# OSO-SCAP-B1-01_Minimalist_SAMD11_Sensor_.net
KiCad netlist of a schematic drawn in EAGLE
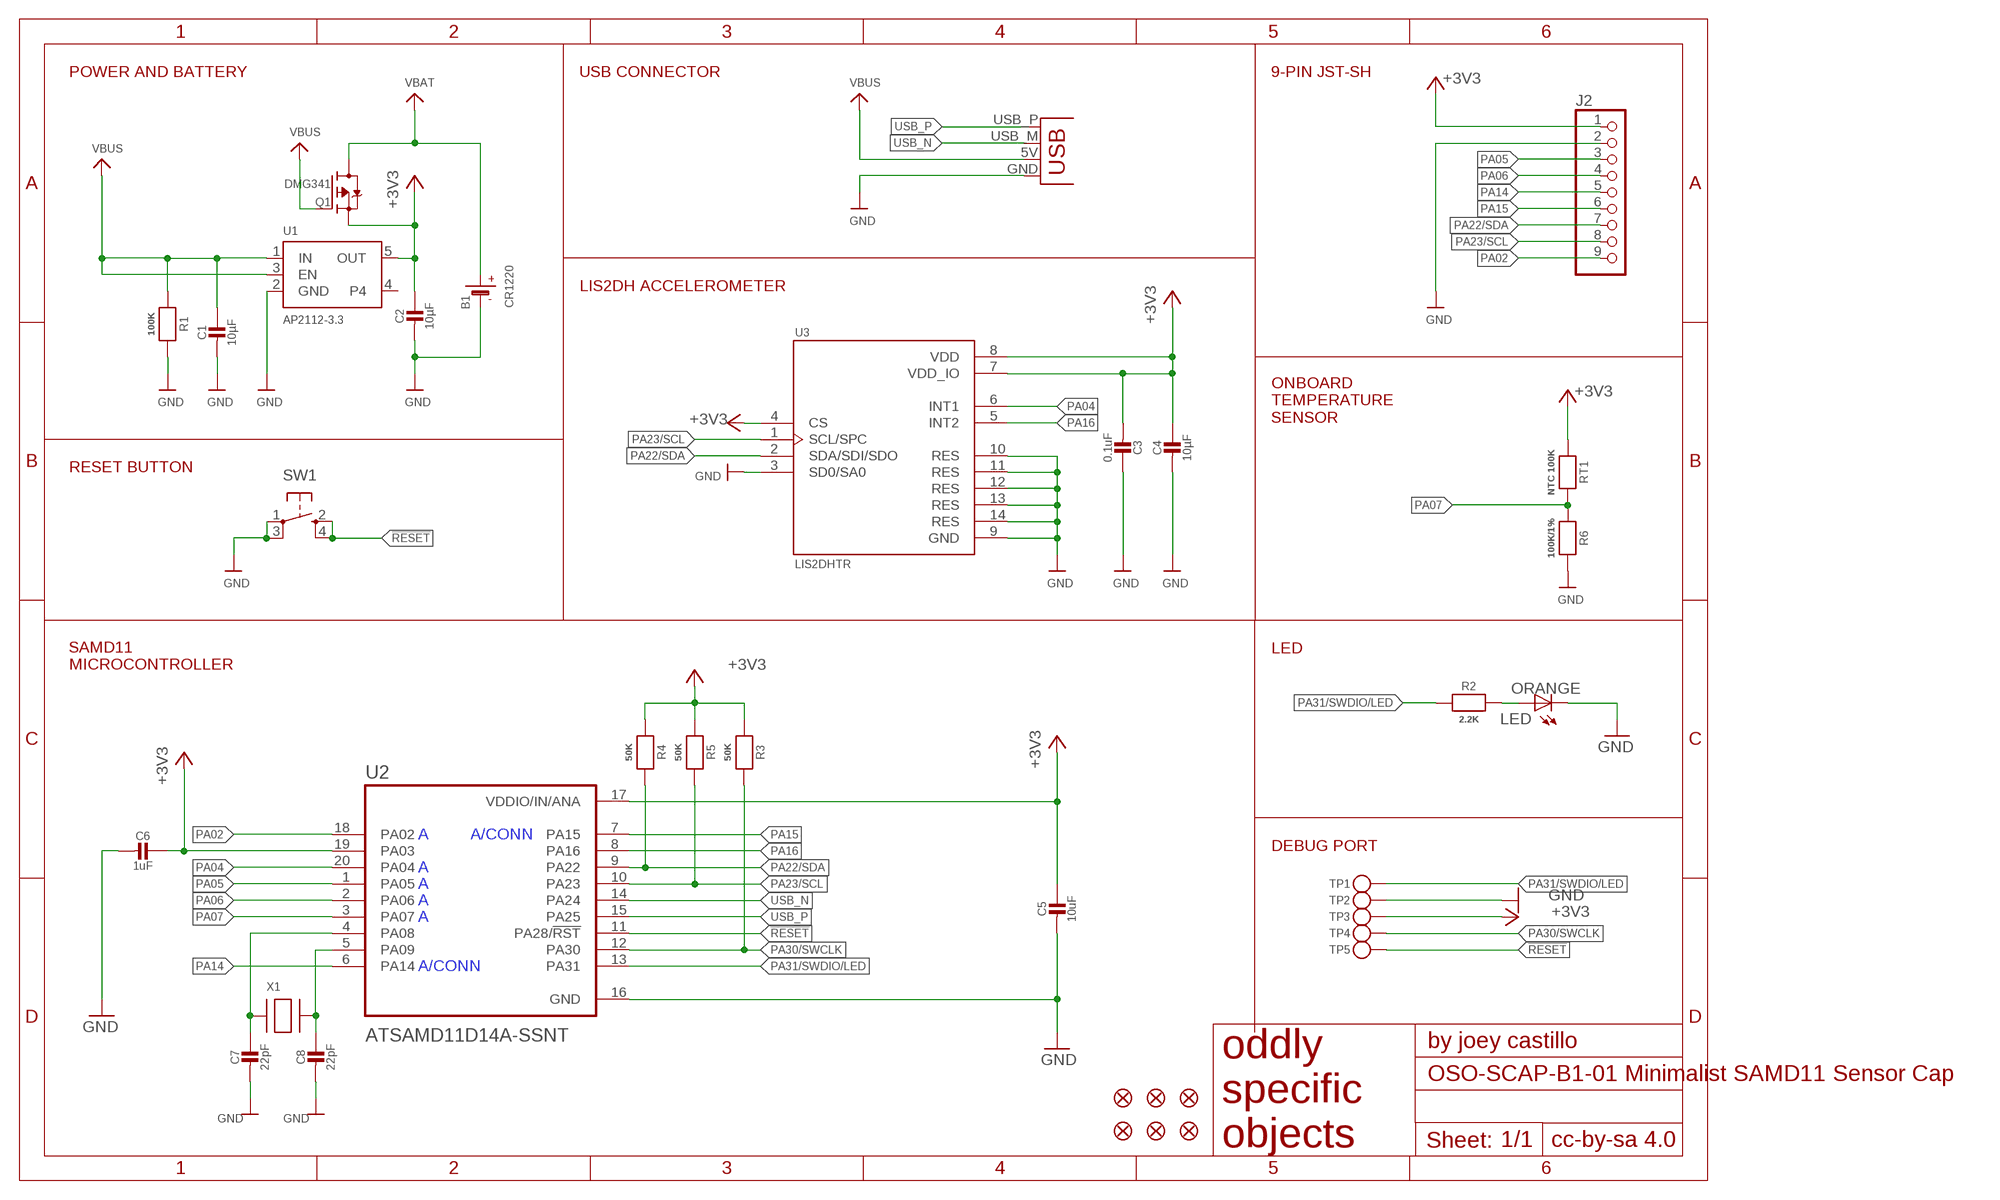
[diagram p0: schematic, sheet 1]

(export (version "E")
  (design (tool "Eeschema 10.0.6"))
  (components
    (comp (ref "B1")
      (value "CR1220")
      (footprint "eagle-import:CR1220")
      (libsource (lib "eagle-import") (part "BATTERYCR1220_SMT"))
    )
    (comp (ref "C1")
      (value "10µF")
      (footprint "eagle-import:0805-NO")
      (libsource (lib "eagle-import") (part "CAP_CERAMIC0805-NOOUTLINE"))
    )
    (comp (ref "C2")
      (value "10µF")
      (footprint "eagle-import:0805-NO")
      (libsource (lib "eagle-import") (part "CAP_CERAMIC0805-NOOUTLINE"))
    )
    (comp (ref "C3")
      (value "0.1uF")
      (footprint "eagle-import:0805-NO")
      (libsource (lib "eagle-import") (part "CAP_CERAMIC0805-NOOUTLINE"))
    )
    (comp (ref "C4")
      (value "10µF")
      (footprint "eagle-import:0805-NO")
      (libsource (lib "eagle-import") (part "CAP_CERAMIC0805-NOOUTLINE"))
    )
    (comp (ref "C5")
      (value "10uF")
      (footprint "eagle-import:0805-NO")
      (libsource (lib "eagle-import") (part "CAP_CERAMIC0805-NOOUTLINE"))
    )
    (comp (ref "C6")
      (value "1uF")
      (footprint "eagle-import:0805-NO")
      (libsource (lib "eagle-import") (part "CAP_CERAMIC0805-NOOUTLINE"))
    )
    (comp (ref "C7")
      (value "22pF")
      (footprint "eagle-import:0805-NO")
      (libsource (lib "eagle-import") (part "CAP_CERAMIC0805-NOOUTLINE"))
    )
    (comp (ref "C8")
      (value "22pF")
      (footprint "eagle-import:0805-NO")
      (libsource (lib "eagle-import") (part "CAP_CERAMIC0805-NOOUTLINE"))
    )
    (comp (ref "FID1")
      (value "FIDUCIAL_1MM")
      (footprint "eagle-import:FIDUCIAL_1MM")
      (libsource (lib "eagle-import") (part "FIDUCIAL_1MM"))
    )
    (comp (ref "FID2")
      (value "FIDUCIAL_1MM")
      (footprint "eagle-import:FIDUCIAL_1MM")
      (libsource (lib "eagle-import") (part "FIDUCIAL_1MM"))
    )
    (comp (ref "FID3")
      (value "FIDUCIAL_1MM")
      (footprint "eagle-import:FIDUCIAL_1MM")
      (libsource (lib "eagle-import") (part "FIDUCIAL_1MM"))
    )
    (comp (ref "FID4")
      (value "FIDUCIAL_1MM")
      (footprint "eagle-import:FIDUCIAL_1MM")
      (libsource (lib "eagle-import") (part "FIDUCIAL_1MM"))
    )
    (comp (ref "FID5")
      (value "FIDUCIAL_1MM")
      (footprint "eagle-import:FIDUCIAL_1MM")
      (libsource (lib "eagle-import") (part "FIDUCIAL_1MM"))
    )
    (comp (ref "FID6")
      (value "FIDUCIAL_1MM")
      (footprint "eagle-import:FIDUCIAL_1MM")
      (libsource (lib "eagle-import") (part "FIDUCIAL_1MM"))
    )
    (comp (ref "J1")
      (value "USBPCB")
      (footprint "eagle-import:USB-A-PCB")
      (libsource (lib "eagle-import") (part "USBPCB"))
    )
    (comp (ref "J2")
      (value "HEADER-1X9_JSTSH")
      (footprint "eagle-import:JST_SH9")
      (libsource (lib "eagle-import") (part "HEADER-1X9_JSTSH"))
    )
    (comp (ref "LED")
      (value "ORANGE")
      (footprint "eagle-import:CHIP-LED0805")
      (libsource (lib "eagle-import") (part "LEDCHIP-LED0805"))
    )
    (comp (ref "Q1")
      (value "DMG341")
      (footprint "eagle-import:SOT23-R")
      (libsource (lib "eagle-import") (part "MOSFET-P"))
    )
    (comp (ref "R1")
      (value "100K")
      (footprint "eagle-import:0805-NO")
      (libsource (lib "eagle-import") (part "RESISTOR0805_NOOUTLINE"))
    )
    (comp (ref "R2")
      (value "2.2K")
      (footprint "eagle-import:0805-NO")
      (libsource (lib "eagle-import") (part "RESISTOR0805_NOOUTLINE"))
    )
    (comp (ref "R3")
      (value "50K")
      (footprint "eagle-import:0805-NO")
      (libsource (lib "eagle-import") (part "RESISTOR0805_NOOUTLINE"))
    )
    (comp (ref "R4")
      (value "50K")
      (footprint "eagle-import:0805-NO")
      (libsource (lib "eagle-import") (part "RESISTOR0805_NOOUTLINE"))
    )
    (comp (ref "R5")
      (value "50K")
      (footprint "eagle-import:0805-NO")
      (libsource (lib "eagle-import") (part "RESISTOR0805_NOOUTLINE"))
    )
    (comp (ref "R6")
      (value "100K/1%")
      (footprint "eagle-import:0805-NO")
      (libsource (lib "eagle-import") (part "RESISTOR0805_NOOUTLINE"))
    )
    (comp (ref "RT1")
      (value "NTC 100K")
      (footprint "eagle-import:0805-NO")
      (libsource (lib "eagle-import") (part "RESISTOR0805_NOOUTLINE"))
    )
    (comp (ref "SW1")
      (value "SPST_TACT-KMR2")
      (footprint "eagle-import:KMR2")
      (libsource (lib "eagle-import") (part "SPST_TACT-KMR2"))
    )
    (comp (ref "TP1")
      (value "TESTPOINTROUND2MMNO")
      (footprint "eagle-import:TESTPOINT_ROUND_2MM_NO")
      (libsource (lib "eagle-import") (part "TESTPOINTROUND2MMNO"))
    )
    (comp (ref "TP2")
      (value "TESTPOINTROUND2MMNO")
      (footprint "eagle-import:TESTPOINT_ROUND_2MM_NO")
      (libsource (lib "eagle-import") (part "TESTPOINTROUND2MMNO"))
    )
    (comp (ref "TP3")
      (value "TESTPOINTROUND2MMNO")
      (footprint "eagle-import:TESTPOINT_ROUND_2MM_NO")
      (libsource (lib "eagle-import") (part "TESTPOINTROUND2MMNO"))
    )
    (comp (ref "TP4")
      (value "TESTPOINTROUND2MMNO")
      (footprint "eagle-import:TESTPOINT_ROUND_2MM_NO")
      (libsource (lib "eagle-import") (part "TESTPOINTROUND2MMNO"))
    )
    (comp (ref "TP5")
      (value "TESTPOINTROUND2MMNO")
      (footprint "eagle-import:TESTPOINT_ROUND_2MM_NO")
      (libsource (lib "eagle-import") (part "TESTPOINTROUND2MMNO"))
    )
    (comp (ref "U1")
      (value "AP2112-3.3")
      (footprint "eagle-import:SOT23-5")
      (libsource (lib "eagle-import") (part "VREG_SOT23-5"))
    )
    (comp (ref "U2")
      (value "ATSAMD11D14A-SSNT")
      (footprint "eagle-import:SOIC127P1030X265-20N")
      (fields (field (name "MF") "Microchip"))
      (libsource (lib "eagle-import") (part "ATSAMD11D14A-SSNT"))
    )
    (comp (ref "U3")
      (value "LIS2DHTR")
      (footprint "eagle-import:PQFN35P200X200X100-14N")
      (fields (field (name "DIGI-KEY_PART_NUMBER") "497-13795-1-ND") (field (name "MF") "STMicroelectronics"))
      (libsource (lib "eagle-import") (part "LIS2DHTR"))
    )
    (comp (ref "X1")
      (value "XTAL-3.2X1.5")
      (footprint "eagle-import:XTAL3215")
      (libsource (lib "eagle-import") (part "XTAL-3.2X1.5"))
    )
  )
  (nets
    (net (code "1") (name "+3V3") (class "Default")
      (node (ref "C2") (pin "1") (pinfunction "1_1") (pintype "passive"))
      (node (ref "C3") (pin "2") (pinfunction "2_2") (pintype "passive"))
      (node (ref "C4") (pin "1") (pinfunction "1_1") (pintype "passive"))
      (node (ref "C5") (pin "1") (pinfunction "1_1") (pintype "passive"))
      (node (ref "C6") (pin "1") (pinfunction "1_1") (pintype "passive"))
      (node (ref "J2") (pin "1") (pinfunction "1_1") (pintype "passive"))
      (node (ref "Q1") (pin "2") (pinfunction "S_2") (pintype "passive"))
      (node (ref "R3") (pin "1") (pinfunction "1_1") (pintype "passive"))
      (node (ref "R4") (pin "1") (pinfunction "1_1") (pintype "passive"))
      (node (ref "R5") (pin "1") (pinfunction "1_1") (pintype "passive"))
      (node (ref "RT1") (pin "1") (pinfunction "1_1") (pintype "passive"))
      (node (ref "TP3") (pin "P$1") (pinfunction "P$1_P$1") (pintype "bidirectional"))
      (node (ref "U1") (pin "5") (pinfunction "OUT_5") (pintype "power_in"))
      (node (ref "U2") (pin "17") (pinfunction "VDDIO/IN/ANA_17") (pintype "power_in"))
      (node (ref "U2") (pin "19") (pinfunction "PA03_19") (pintype "bidirectional"))
      (node (ref "U3") (pin "4") (pinfunction "CS_4") (pintype "input"))
      (node (ref "U3") (pin "7") (pinfunction "VDD_IO_7") (pintype "power_in"))
      (node (ref "U3") (pin "8") (pinfunction "VDD_8") (pintype "power_in"))
    )
    (net (code "2") (name "/~{RESET}") (class "Default")
      (node (ref "SW1") (pin "2") (pinfunction "S_2") (pintype "passive"))
      (node (ref "SW1") (pin "4") (pinfunction "S1_4") (pintype "passive"))
      (node (ref "TP5") (pin "P$1") (pinfunction "P$1_P$1") (pintype "bidirectional"))
      (node (ref "U2") (pin "11") (pinfunction "PA28/~{RST}_11") (pintype "bidirectional"))
    )
    (net (code "3") (name "GND") (class "Default")
      (node (ref "B1") (pin "-") (pinfunction "-_-") (pintype "passive"))
      (node (ref "C1") (pin "2") (pinfunction "2_2") (pintype "passive"))
      (node (ref "C2") (pin "2") (pinfunction "2_2") (pintype "passive"))
      (node (ref "C3") (pin "1") (pinfunction "1_1") (pintype "passive"))
      (node (ref "C4") (pin "2") (pinfunction "2_2") (pintype "passive"))
      (node (ref "C5") (pin "2") (pinfunction "2_2") (pintype "passive"))
      (node (ref "C6") (pin "2") (pinfunction "2_2") (pintype "passive"))
      (node (ref "C7") (pin "2") (pinfunction "2_2") (pintype "passive"))
      (node (ref "C8") (pin "2") (pinfunction "2_2") (pintype "passive"))
      (node (ref "J1") (pin "GND") (pinfunction "GND_GND") (pintype "bidirectional"))
      (node (ref "J2") (pin "2") (pinfunction "2_2") (pintype "passive"))
      (node (ref "LED") (pin "C") (pinfunction "C_C") (pintype "passive"))
      (node (ref "R1") (pin "2") (pinfunction "2_2") (pintype "passive"))
      (node (ref "R6") (pin "2") (pinfunction "2_2") (pintype "passive"))
      (node (ref "SW1") (pin "1") (pinfunction "P_1") (pintype "passive"))
      (node (ref "SW1") (pin "3") (pinfunction "P1_3") (pintype "passive"))
      (node (ref "TP2") (pin "P$1") (pinfunction "P$1_P$1") (pintype "bidirectional"))
      (node (ref "U1") (pin "2") (pinfunction "GND_2") (pintype "power_in"))
      (node (ref "U2") (pin "16") (pinfunction "GND_16") (pintype "power_in"))
      (node (ref "U3") (pin "10") (pinfunction "RES_10") (pintype "power_in"))
      (node (ref "U3") (pin "11") (pinfunction "RES_11") (pintype "power_in"))
      (node (ref "U3") (pin "12") (pinfunction "RES_12") (pintype "power_in"))
      (node (ref "U3") (pin "13") (pinfunction "RES_13") (pintype "power_in"))
      (node (ref "U3") (pin "14") (pinfunction "RES_14") (pintype "power_in"))
      (node (ref "U3") (pin "3") (pinfunction "SD0/SA0_3") (pintype "output"))
      (node (ref "U3") (pin "9") (pinfunction "GND_9") (pintype "power_in"))
    )
    (net (code "4") (name "Net-(LED-PadA)") (class "Default")
      (node (ref "LED") (pin "A") (pinfunction "A_A") (pintype "passive"))
      (node (ref "R2") (pin "2") (pinfunction "2_2") (pintype "passive"))
    )
    (net (code "5") (name "Net-(U2-PA08)") (class "Default")
      (node (ref "C7") (pin "1") (pinfunction "1_1") (pintype "passive"))
      (node (ref "U2") (pin "4") (pinfunction "PA08_4") (pintype "bidirectional"))
      (node (ref "X1") (pin "P$1") (pinfunction "P$1_P$1") (pintype "bidirectional"))
    )
    (net (code "6") (name "Net-(U2-PA09)") (class "Default")
      (node (ref "C8") (pin "1") (pinfunction "1_1") (pintype "passive"))
      (node (ref "U2") (pin "5") (pinfunction "PA09_5") (pintype "bidirectional"))
      (node (ref "X1") (pin "P$2") (pinfunction "P$2_P$2") (pintype "bidirectional"))
    )
    (net (code "7") (name "PA02") (class "Default")
      (node (ref "J2") (pin "9") (pinfunction "9_9") (pintype "passive"))
      (node (ref "U2") (pin "18") (pinfunction "PA02_18") (pintype "bidirectional"))
    )
    (net (code "8") (name "PA04") (class "Default")
      (node (ref "U2") (pin "20") (pinfunction "PA04_20") (pintype "bidirectional"))
      (node (ref "U3") (pin "6") (pinfunction "INT1_6") (pintype "output"))
    )
    (net (code "9") (name "PA05") (class "Default")
      (node (ref "J2") (pin "3") (pinfunction "3_3") (pintype "passive"))
      (node (ref "U2") (pin "1") (pinfunction "PA05_1") (pintype "bidirectional"))
    )
    (net (code "10") (name "PA06") (class "Default")
      (node (ref "J2") (pin "4") (pinfunction "4_4") (pintype "passive"))
      (node (ref "U2") (pin "2") (pinfunction "PA06_2") (pintype "bidirectional"))
    )
    (net (code "11") (name "PA07") (class "Default")
      (node (ref "R6") (pin "1") (pinfunction "1_1") (pintype "passive"))
      (node (ref "RT1") (pin "2") (pinfunction "2_2") (pintype "passive"))
      (node (ref "U2") (pin "3") (pinfunction "PA07_3") (pintype "bidirectional"))
    )
    (net (code "12") (name "PA14") (class "Default")
      (node (ref "J2") (pin "5") (pinfunction "5_5") (pintype "passive"))
      (node (ref "U2") (pin "6") (pinfunction "PA14_6") (pintype "bidirectional"))
    )
    (net (code "13") (name "PA15") (class "Default")
      (node (ref "J2") (pin "6") (pinfunction "6_6") (pintype "passive"))
      (node (ref "U2") (pin "7") (pinfunction "PA15_7") (pintype "bidirectional"))
    )
    (net (code "14") (name "PA16") (class "Default")
      (node (ref "U2") (pin "8") (pinfunction "PA16_8") (pintype "bidirectional"))
      (node (ref "U3") (pin "5") (pinfunction "INT2_5") (pintype "output"))
    )
    (net (code "15") (name "PA22{slash}SDA") (class "Default")
      (node (ref "J2") (pin "7") (pinfunction "7_7") (pintype "passive"))
      (node (ref "R4") (pin "2") (pinfunction "2_2") (pintype "passive"))
      (node (ref "U2") (pin "9") (pinfunction "PA22_9") (pintype "bidirectional"))
      (node (ref "U3") (pin "2") (pinfunction "SDA/SDI/SDO_2") (pintype "bidirectional"))
    )
    (net (code "16") (name "PA23{slash}SCL") (class "Default")
      (node (ref "J2") (pin "8") (pinfunction "8_8") (pintype "passive"))
      (node (ref "R5") (pin "2") (pinfunction "2_2") (pintype "passive"))
      (node (ref "U2") (pin "10") (pinfunction "PA23_10") (pintype "bidirectional"))
      (node (ref "U3") (pin "1") (pinfunction "SCL/SPC_1") (pintype "input"))
    )
    (net (code "17") (name "PA30{slash}SWCLK") (class "Default")
      (node (ref "R3") (pin "2") (pinfunction "2_2") (pintype "passive"))
      (node (ref "TP4") (pin "P$1") (pinfunction "P$1_P$1") (pintype "bidirectional"))
      (node (ref "U2") (pin "12") (pinfunction "PA30_12") (pintype "bidirectional"))
    )
    (net (code "18") (name "PA31{slash}SWDIO{slash}LED") (class "Default")
      (node (ref "R2") (pin "1") (pinfunction "1_1") (pintype "passive"))
      (node (ref "TP1") (pin "P$1") (pinfunction "P$1_P$1") (pintype "bidirectional"))
      (node (ref "U2") (pin "13") (pinfunction "PA31_13") (pintype "bidirectional"))
    )
    (net (code "19") (name "USB_N") (class "Default")
      (node (ref "J1") (pin "USB_M") (pinfunction "D-_USB_M") (pintype "bidirectional"))
      (node (ref "U2") (pin "14") (pinfunction "PA24_14") (pintype "bidirectional"))
    )
    (net (code "20") (name "USB_P") (class "Default")
      (node (ref "J1") (pin "USB_P") (pinfunction "D+_USB_P") (pintype "bidirectional"))
      (node (ref "U2") (pin "15") (pinfunction "PA25_15") (pintype "bidirectional"))
    )
    (net (code "21") (name "VBAT") (class "Default")
      (node (ref "B1") (pin "+$1") (pinfunction "+_+$1") (pintype "passive"))
      (node (ref "B1") (pin "+$2") (pinfunction "+_+$2") (pintype "passive"))
      (node (ref "Q1") (pin "3") (pinfunction "D_3") (pintype "passive"))
    )
    (net (code "22") (name "VBUS") (class "Default")
      (node (ref "C1") (pin "1") (pinfunction "1_1") (pintype "passive"))
      (node (ref "J1") (pin "5V") (pinfunction "VBUS_5V") (pintype "bidirectional"))
      (node (ref "Q1") (pin "1") (pinfunction "G_1") (pintype "passive"))
      (node (ref "R1") (pin "1") (pinfunction "1_1") (pintype "passive"))
      (node (ref "U1") (pin "1") (pinfunction "IN_1") (pintype "power_in"))
      (node (ref "U1") (pin "3") (pinfunction "EN_3") (pintype "input"))
    )
    (net (code "23") (name "unconnected-(U1-P4-Pad4)") (class "Default")
      (node (ref "U1") (pin "4") (pinfunction "P4_4") (pintype "bidirectional"))
    )
  )
)
